# Actuator-MKI-3.net
KiCad netlist of a schematic drawn in EAGLE
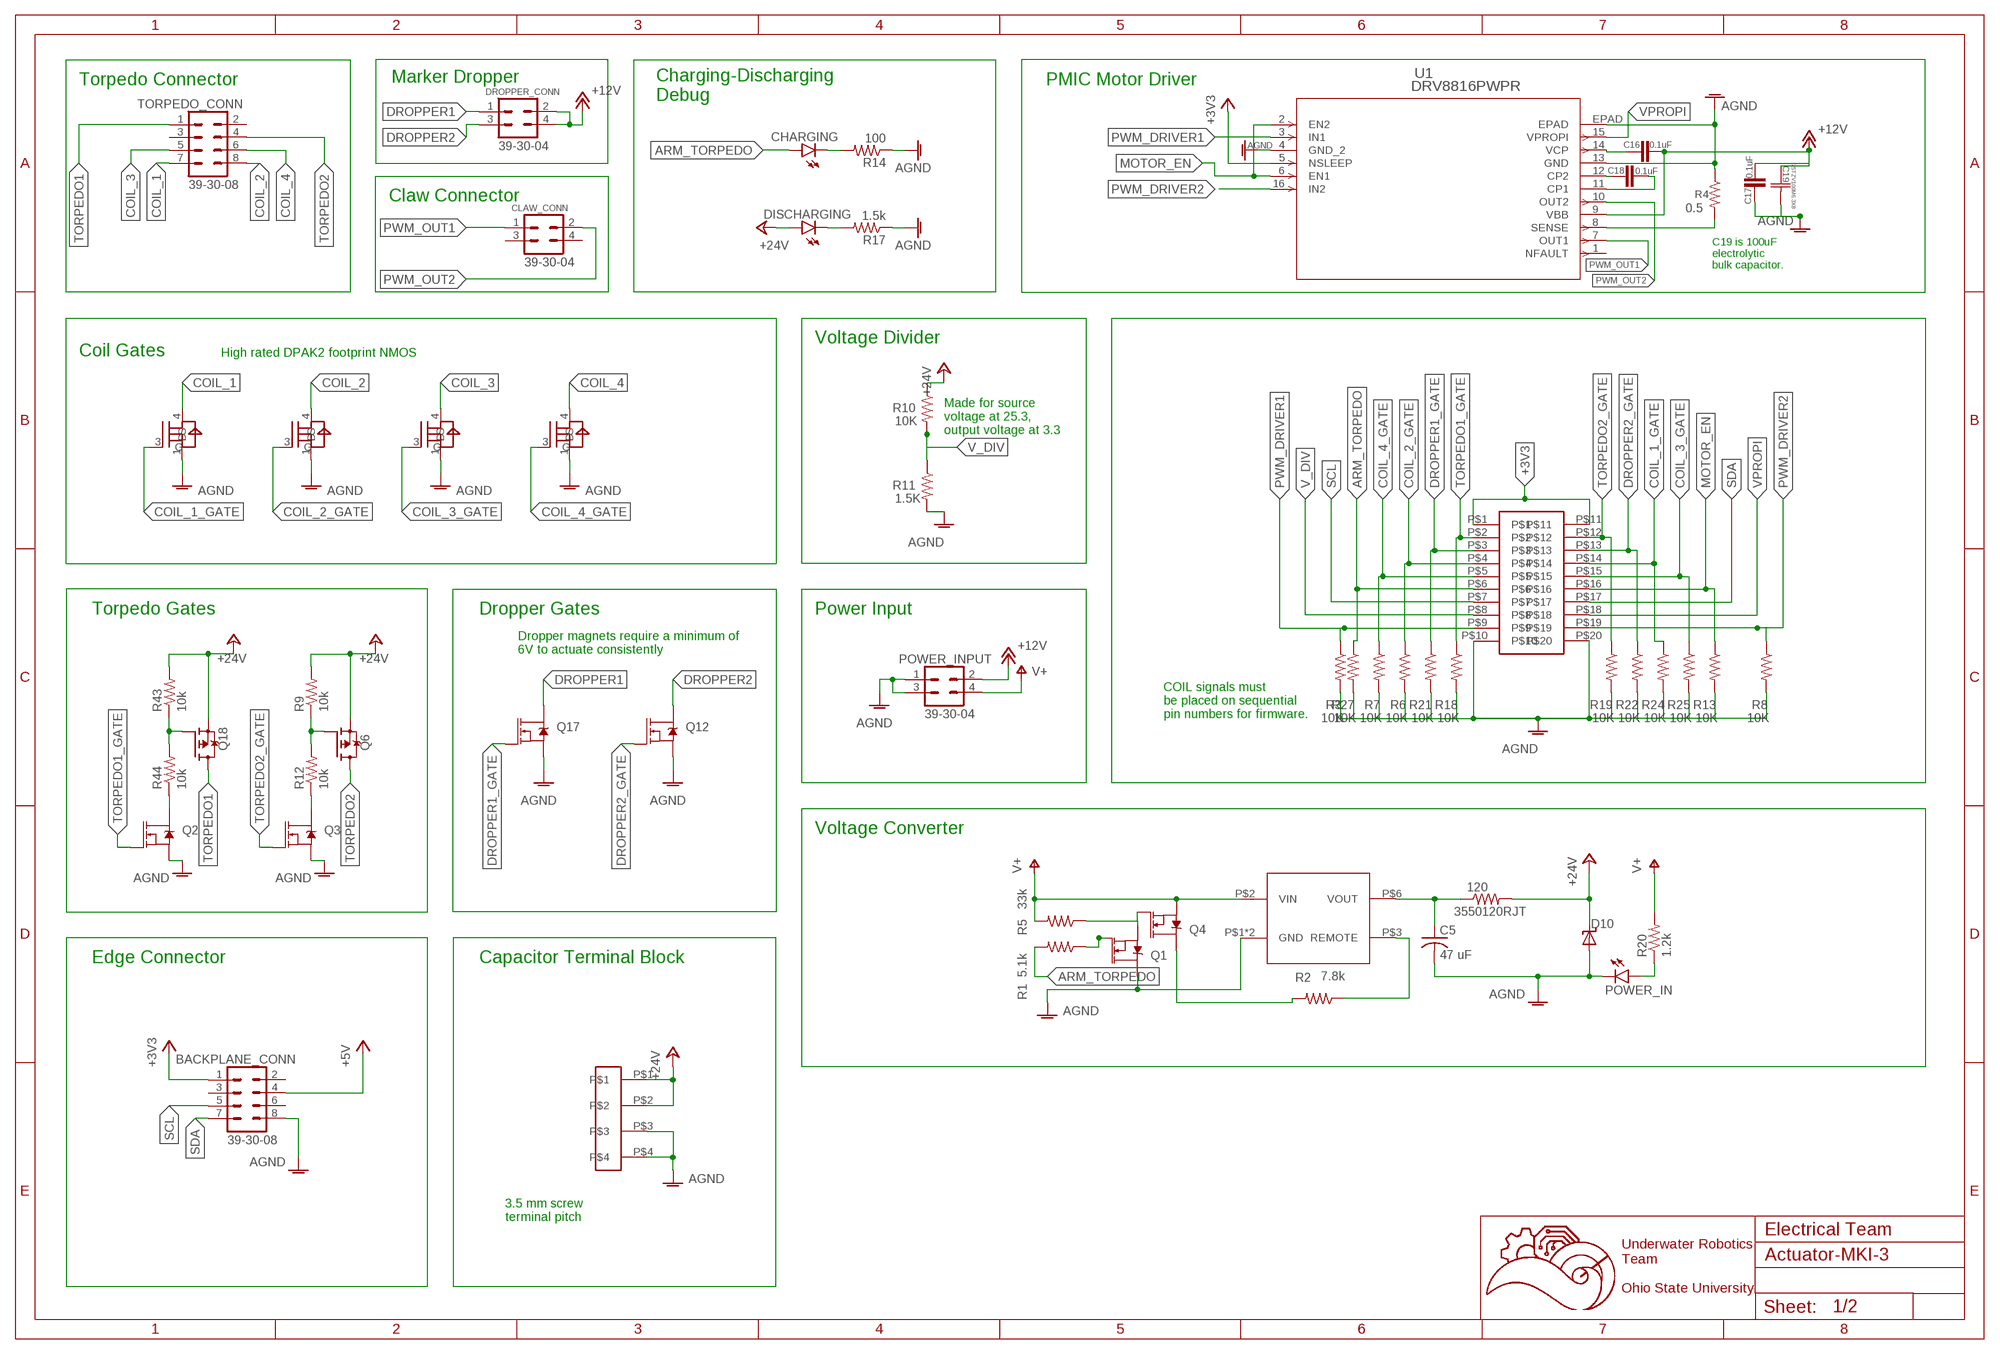
[diagram p0: schematic, sheet 1]
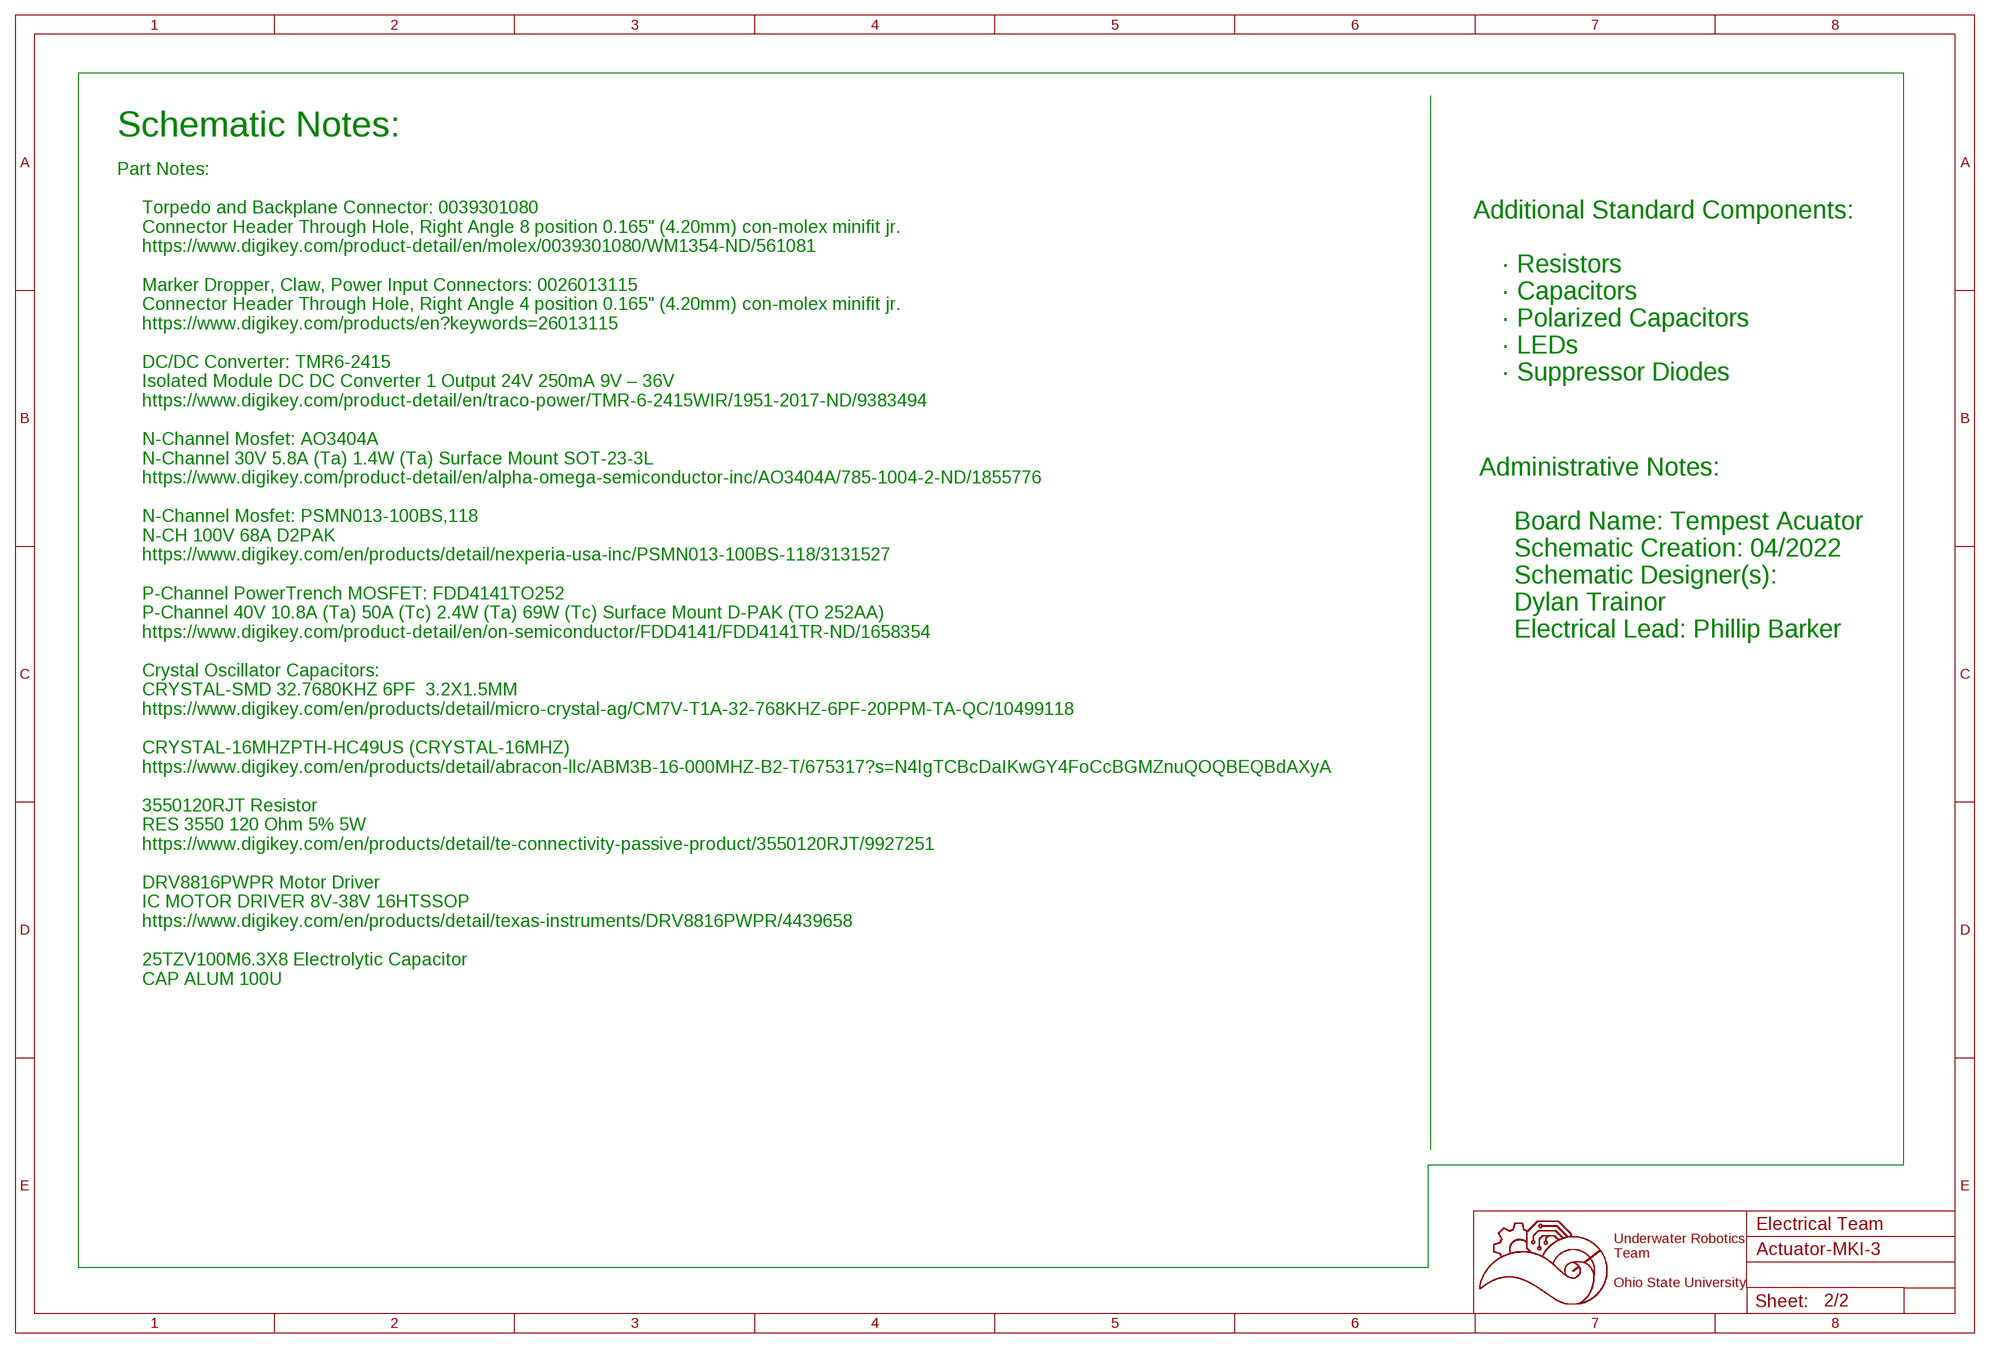
[diagram p1: schematic, sheet 2]

(export (version "E")
  (design (tool "Eeschema 10.0.6"))
  (components
    (comp (ref "120")
      (value "3550120RJT")
      (footprint "eagle-import:3550120RJT")
      (libsource (lib "eagle-import") (part "3550120RJT"))
    )
    (comp (ref "BACKPLANE_CONN")
      (value "39-30-08")
      (footprint "eagle-import:39-30-_08_")
      (libsource (lib "eagle-import") (part "39-30-?08?"))
    )
    (comp (ref "C5")
      (value "47 uF")
      (footprint "eagle-import:C1206K")
      (libsource (lib "eagle-import") (part "C-USC1206K"))
    )
    (comp (ref "C16")
      (value "0.1uF")
      (footprint "eagle-import:C0603")
      (libsource (lib "eagle-import") (part "C-EUC0603"))
    )
    (comp (ref "C17")
      (value "0.1uF")
      (footprint "eagle-import:C0603")
      (libsource (lib "eagle-import") (part "C-EUC0603"))
    )
    (comp (ref "C18")
      (value "0.1uF")
      (footprint "eagle-import:C0603")
      (libsource (lib "eagle-import") (part "C-EUC0603"))
    )
    (comp (ref "C19")
      (value "25TZV100M6.3X8")
      (footprint "eagle-import:CAP_J-V_6P3X8_RUB")
      (fields (field (name "COPYRIGHT") "Copyright (C) 2018 Accelerated Designs. All rights reserved"))
      (libsource (lib "eagle-import") (part "25TZV100M6.3X8"))
    )
    (comp (ref "CHARGING")
      (value "LEDCHIPLED_0603")
      (footprint "eagle-import:CHIPLED_0603")
      (libsource (lib "eagle-import") (part "LEDCHIPLED_0603"))
    )
    (comp (ref "CLAW_CONN")
      (value "39-30-04")
      (footprint "eagle-import:39-30-_04_")
      (libsource (lib "eagle-import") (part "39-30-?04?"))
    )
    (comp (ref "D10")
      (value "SUPPRESSOR-SMBJ")
      (footprint "eagle-import:SMBJ")
      (libsource (lib "eagle-import") (part "SUPPRESSOR-SMBJ"))
    )
    (comp (ref "DISCHARGING")
      (value "LEDCHIPLED_0603")
      (footprint "eagle-import:CHIPLED_0603")
      (libsource (lib "eagle-import") (part "LEDCHIPLED_0603"))
    )
    (comp (ref "DROPPER_CONN")
      (value "39-30-04")
      (footprint "eagle-import:39-30-_04_")
      (libsource (lib "eagle-import") (part "39-30-?04?"))
    )
    (comp (ref "POWER_IN")
      (value "LEDCHIPLED_0603")
      (footprint "eagle-import:CHIPLED_0603")
      (libsource (lib "eagle-import") (part "LEDCHIPLED_0603"))
    )
    (comp (ref "POWER_INPUT")
      (value "39-30-04")
      (footprint "eagle-import:39-30-_04_")
      (libsource (lib "eagle-import") (part "39-30-?04?"))
    )
    (comp (ref "Q1")
      (value "MOSFET-NCH-AO3404A")
      (footprint "eagle-import:SOT23-3")
      (libsource (lib "eagle-import") (part "MOSFET-NCH-AO3404A"))
    )
    (comp (ref "Q2")
      (value "MOSFET-NCH-AO3404A")
      (footprint "eagle-import:SOT23-3")
      (libsource (lib "eagle-import") (part "MOSFET-NCH-AO3404A"))
    )
    (comp (ref "Q3")
      (value "MOSFET-NCH-AO3404A")
      (footprint "eagle-import:SOT23-3")
      (libsource (lib "eagle-import") (part "MOSFET-NCH-AO3404A"))
    )
    (comp (ref "Q4")
      (value "MOSFET-NCH-AO3404A")
      (footprint "eagle-import:SOT23-3")
      (libsource (lib "eagle-import") (part "MOSFET-NCH-AO3404A"))
    )
    (comp (ref "Q6")
      (value "FDD4141TO252")
      (footprint "eagle-import:TO252")
      (libsource (lib "eagle-import") (part "FDD4141TO252"))
    )
    (comp (ref "Q12")
      (value "MOSFET-NCH-AO3404A")
      (footprint "eagle-import:SOT23-3")
      (libsource (lib "eagle-import") (part "MOSFET-NCH-AO3404A"))
    )
    (comp (ref "Q17")
      (value "MOSFET-NCH-AO3404A")
      (footprint "eagle-import:SOT23-3")
      (libsource (lib "eagle-import") (part "MOSFET-NCH-AO3404A"))
    )
    (comp (ref "Q18")
      (value "FDD4141TO252")
      (footprint "eagle-import:TO252")
      (libsource (lib "eagle-import") (part "FDD4141TO252"))
    )
    (comp (ref "R1")
      (value "5.1k")
      (footprint "eagle-import:R0603")
      (libsource (lib "eagle-import") (part "R-US_R0603"))
    )
    (comp (ref "R2")
      (value "7.8k")
      (footprint "eagle-import:R0603")
      (libsource (lib "eagle-import") (part "R-US_R0603"))
    )
    (comp (ref "R3")
      (value "10K")
      (footprint "eagle-import:R0603")
      (libsource (lib "eagle-import") (part "R-US_R0603"))
    )
    (comp (ref "R4")
      (value "0.5")
      (footprint "eagle-import:R0805")
      (libsource (lib "eagle-import") (part "R-US_R0805"))
    )
    (comp (ref "R5")
      (value "33k")
      (footprint "eagle-import:R0603")
      (libsource (lib "eagle-import") (part "R-US_R0603"))
    )
    (comp (ref "R6")
      (value "10K")
      (footprint "eagle-import:R0603")
      (libsource (lib "eagle-import") (part "R-US_R0603"))
    )
    (comp (ref "R7")
      (value "10K")
      (footprint "eagle-import:R0603")
      (libsource (lib "eagle-import") (part "R-US_R0603"))
    )
    (comp (ref "R8")
      (value "10K")
      (footprint "eagle-import:R0603")
      (libsource (lib "eagle-import") (part "R-US_R0603"))
    )
    (comp (ref "R9")
      (value "10k")
      (footprint "eagle-import:R0603")
      (libsource (lib "eagle-import") (part "R-US_R0603"))
    )
    (comp (ref "R10")
      (value "10K")
      (footprint "eagle-import:R0603")
      (libsource (lib "eagle-import") (part "R-US_R0603"))
    )
    (comp (ref "R11")
      (value "1.5K")
      (footprint "eagle-import:R0603")
      (libsource (lib "eagle-import") (part "R-US_R0603"))
    )
    (comp (ref "R12")
      (value "10k")
      (footprint "eagle-import:R0603")
      (libsource (lib "eagle-import") (part "R-US_R0603"))
    )
    (comp (ref "R13")
      (value "10K")
      (footprint "eagle-import:R0603")
      (libsource (lib "eagle-import") (part "R-US_R0603"))
    )
    (comp (ref "R14")
      (value "100")
      (footprint "eagle-import:R0805")
      (libsource (lib "eagle-import") (part "R-US_R0805"))
    )
    (comp (ref "R17")
      (value "1.5k")
      (footprint "eagle-import:R0805")
      (libsource (lib "eagle-import") (part "R-US_R0805"))
    )
    (comp (ref "R18")
      (value "10K")
      (footprint "eagle-import:R0603")
      (libsource (lib "eagle-import") (part "R-US_R0603"))
    )
    (comp (ref "R19")
      (value "10K")
      (footprint "eagle-import:R0603")
      (libsource (lib "eagle-import") (part "R-US_R0603"))
    )
    (comp (ref "R20")
      (value "1.2k")
      (footprint "eagle-import:R0805")
      (libsource (lib "eagle-import") (part "R-US_R0805"))
    )
    (comp (ref "R21")
      (value "10K")
      (footprint "eagle-import:R0603")
      (libsource (lib "eagle-import") (part "R-US_R0603"))
    )
    (comp (ref "R22")
      (value "10K")
      (footprint "eagle-import:R0603")
      (libsource (lib "eagle-import") (part "R-US_R0603"))
    )
    (comp (ref "R24")
      (value "10K")
      (footprint "eagle-import:R0603")
      (libsource (lib "eagle-import") (part "R-US_R0603"))
    )
    (comp (ref "R25")
      (value "10K")
      (footprint "eagle-import:R0603")
      (libsource (lib "eagle-import") (part "R-US_R0603"))
    )
    (comp (ref "R27")
      (value "10K")
      (footprint "eagle-import:R0603")
      (libsource (lib "eagle-import") (part "R-US_R0603"))
    )
    (comp (ref "R43")
      (value "10k")
      (footprint "eagle-import:R0603")
      (libsource (lib "eagle-import") (part "R-US_R0603"))
    )
    (comp (ref "R44")
      (value "10k")
      (footprint "eagle-import:R0603")
      (libsource (lib "eagle-import") (part "R-US_R0603"))
    )
    (comp (ref "TORPEDO_CONN")
      (value "39-30-08")
      (footprint "eagle-import:39-30-_08_")
      (libsource (lib "eagle-import") (part "39-30-?08?"))
    )
    (comp (ref "U$1")
      (value "31059104")
      (footprint "eagle-import:31059104")
      (libsource (lib "eagle-import") (part "31059104"))
    )
    (comp (ref "U$2")
      (value "JTAG-SMD")
      (footprint "eagle-import:JTAG-SMD")
      (libsource (lib "eagle-import") (part "JTAG-SMD"))
    )
    (comp (ref "U$6")
      (value "TMR6-2415")
      (footprint "eagle-import:TMR6-2415")
      (libsource (lib "eagle-import") (part "TMR6-2415"))
    )
    (comp (ref "U1")
      (value "DRV8816PWPR")
      (footprint "eagle-import:PWP_16")
      (libsource (lib "eagle-import") (part "DRV8816PWPR"))
    )
    (comp (ref "U2")
      (value "MBRB2060CTT4G")
      (footprint "eagle-import:D2PAK3-4_9P65X10P29_ONS")
      (libsource (lib "eagle-import") (part "MBRB2060CTT4G"))
    )
    (comp (ref "U3")
      (value "MBRB2060CTT4G")
      (footprint "eagle-import:D2PAK3-4_9P65X10P29_ONS")
      (libsource (lib "eagle-import") (part "MBRB2060CTT4G"))
    )
    (comp (ref "U4")
      (value "MBRB2060CTT4G")
      (footprint "eagle-import:D2PAK3-4_9P65X10P29_ONS")
      (libsource (lib "eagle-import") (part "MBRB2060CTT4G"))
    )
    (comp (ref "U5")
      (value "MBRB2060CTT4G")
      (footprint "eagle-import:D2PAK3-4_9P65X10P29_ONS")
      (libsource (lib "eagle-import") (part "MBRB2060CTT4G"))
    )
  )
  (nets
    (net (code "1") (name "+3V3") (class "Default")
      (node (ref "BACKPLANE_CONN") (pin "1") (pinfunction "1_1") (pintype "passive"))
      (node (ref "U$2") (pin "P$1") (pinfunction "P$1_P$1") (pintype "bidirectional"))
      (node (ref "U$2") (pin "P$11") (pinfunction "P$11_P$11") (pintype "bidirectional"))
      (node (ref "U1") (pin "5") (pinfunction "NSLEEP_5") (pintype "input"))
    )
    (net (code "2") (name "+5V") (class "Default")
      (node (ref "BACKPLANE_CONN") (pin "4") (pinfunction "4_4") (pintype "passive"))
    )
    (net (code "3") (name "+12V") (class "Default")
      (node (ref "C16") (pin "2") (pinfunction "2_2") (pintype "passive"))
      (node (ref "C17") (pin "2") (pinfunction "2_2") (pintype "passive"))
      (node (ref "C19") (pin "1") (pinfunction "1_1") (pintype "passive"))
      (node (ref "DROPPER_CONN") (pin "2") (pinfunction "2_2") (pintype "passive"))
      (node (ref "DROPPER_CONN") (pin "4") (pinfunction "4_4") (pintype "passive"))
      (node (ref "POWER_INPUT") (pin "2") (pinfunction "2_2") (pintype "passive"))
      (node (ref "U1") (pin "9") (pinfunction "VBB_9") (pintype "power_in"))
    )
    (net (code "4") (name "+24V") (class "Default")
      (node (ref "120") (pin "P$2") (pinfunction "2_P$2") (pintype "passive"))
      (node (ref "D10") (pin "C") (pinfunction "C_C") (pintype "passive"))
      (node (ref "DISCHARGING") (pin "A") (pinfunction "A_A") (pintype "passive"))
      (node (ref "Q18") (pin "2") (pinfunction "S_2") (pintype "passive"))
      (node (ref "Q6") (pin "2") (pinfunction "S_2") (pintype "passive"))
      (node (ref "R10") (pin "1") (pinfunction "1_1") (pintype "passive"))
      (node (ref "R43") (pin "2") (pinfunction "2_2") (pintype "passive"))
      (node (ref "R9") (pin "2") (pinfunction "2_2") (pintype "passive"))
      (node (ref "U$1") (pin "P$1") (pinfunction "P$1_P$1") (pintype "bidirectional"))
      (node (ref "U$1") (pin "P$2") (pinfunction "P$2_P$2") (pintype "bidirectional"))
    )
    (net (code "5") (name "AGND") (class "Default")
      (node (ref "BACKPLANE_CONN") (pin "8") (pinfunction "8_8") (pintype "passive"))
      (node (ref "C17") (pin "1") (pinfunction "1_1") (pintype "passive"))
      (node (ref "C19") (pin "2") (pinfunction "2_2") (pintype "passive"))
      (node (ref "C5") (pin "2") (pinfunction "2_2") (pintype "passive"))
      (node (ref "D10") (pin "A") (pinfunction "A_A") (pintype "passive"))
      (node (ref "POWER_IN") (pin "C") (pinfunction "C_C") (pintype "passive"))
      (node (ref "POWER_INPUT") (pin "1") (pinfunction "1_1") (pintype "passive"))
      (node (ref "POWER_INPUT") (pin "3") (pinfunction "3_3") (pintype "passive"))
      (node (ref "Q1") (pin "3") (pinfunction "D_3") (pintype "bidirectional"))
      (node (ref "Q12") (pin "2") (pinfunction "S_2") (pintype "bidirectional"))
      (node (ref "Q17") (pin "2") (pinfunction "S_2") (pintype "bidirectional"))
      (node (ref "Q2") (pin "2") (pinfunction "S_2") (pintype "bidirectional"))
      (node (ref "Q3") (pin "2") (pinfunction "S_2") (pintype "bidirectional"))
      (node (ref "R11") (pin "2") (pinfunction "2_2") (pintype "passive"))
      (node (ref "R13") (pin "2") (pinfunction "2_2") (pintype "passive"))
      (node (ref "R14") (pin "1") (pinfunction "1_1") (pintype "passive"))
      (node (ref "R17") (pin "1") (pinfunction "1_1") (pintype "passive"))
      (node (ref "R18") (pin "2") (pinfunction "2_2") (pintype "passive"))
      (node (ref "R19") (pin "2") (pinfunction "2_2") (pintype "passive"))
      (node (ref "R21") (pin "2") (pinfunction "2_2") (pintype "passive"))
      (node (ref "R22") (pin "2") (pinfunction "2_2") (pintype "passive"))
      (node (ref "R24") (pin "2") (pinfunction "2_2") (pintype "passive"))
      (node (ref "R25") (pin "2") (pinfunction "2_2") (pintype "passive"))
      (node (ref "R27") (pin "2") (pinfunction "2_2") (pintype "passive"))
      (node (ref "R3") (pin "2") (pinfunction "2_2") (pintype "passive"))
      (node (ref "R4") (pin "1") (pinfunction "1_1") (pintype "passive"))
      (node (ref "R6") (pin "2") (pinfunction "2_2") (pintype "passive"))
      (node (ref "R7") (pin "2") (pinfunction "2_2") (pintype "passive"))
      (node (ref "R8") (pin "2") (pinfunction "2_2") (pintype "passive"))
      (node (ref "U$1") (pin "P$3") (pinfunction "P$3_P$3") (pintype "bidirectional"))
      (node (ref "U$1") (pin "P$4") (pinfunction "P$4_P$4") (pintype "bidirectional"))
      (node (ref "U$2") (pin "P$10") (pinfunction "P$10_P$10") (pintype "bidirectional"))
      (node (ref "U$2") (pin "P$20") (pinfunction "P$20_P$20") (pintype "bidirectional"))
      (node (ref "U$6") (pin "P$1") (pinfunction "GND_P$1") (pintype "bidirectional"))
      (node (ref "U$6") (pin "P$7") (pinfunction "GND_P$7") (pintype "bidirectional"))
      (node (ref "U1") (pin "13") (pinfunction "GND_13") (pintype "power_in"))
      (node (ref "U1") (pin "4") (pinfunction "GND_2_4") (pintype "power_in"))
      (node (ref "U1") (pin "EPAD") (pinfunction "EPAD_EPAD") (pintype "passive"))
      (node (ref "U2") (pin "1") (pinfunction "S_1") (pintype "bidirectional"))
      (node (ref "U3") (pin "1") (pinfunction "S_1") (pintype "bidirectional"))
      (node (ref "U4") (pin "1") (pinfunction "S_1") (pintype "bidirectional"))
      (node (ref "U5") (pin "1") (pinfunction "S_1") (pintype "bidirectional"))
    )
    (net (code "6") (name "ARM_TORPEDO") (class "Default")
      (node (ref "CHARGING") (pin "A") (pinfunction "A_A") (pintype "passive"))
      (node (ref "R1") (pin "2") (pinfunction "2_2") (pintype "passive"))
      (node (ref "R27") (pin "1") (pinfunction "1_1") (pintype "passive"))
      (node (ref "U$2") (pin "P$6") (pinfunction "P$6_P$6") (pintype "bidirectional"))
    )
    (net (code "7") (name "COIL_1") (class "Default")
      (node (ref "TORPEDO_CONN") (pin "7") (pinfunction "7_7") (pintype "passive"))
      (node (ref "U2") (pin "4") (pinfunction "D_4") (pintype "bidirectional"))
    )
    (net (code "8") (name "COIL_1_GATE") (class "Default")
      (node (ref "R24") (pin "1") (pinfunction "1_1") (pintype "passive"))
      (node (ref "U$2") (pin "P$14") (pinfunction "P$14_P$14") (pintype "bidirectional"))
      (node (ref "U2") (pin "3") (pinfunction "G_3") (pintype "bidirectional"))
    )
    (net (code "9") (name "COIL_2") (class "Default")
      (node (ref "TORPEDO_CONN") (pin "8") (pinfunction "8_8") (pintype "passive"))
      (node (ref "U3") (pin "4") (pinfunction "D_4") (pintype "bidirectional"))
    )
    (net (code "10") (name "COIL_2_GATE") (class "Default")
      (node (ref "R6") (pin "1") (pinfunction "1_1") (pintype "passive"))
      (node (ref "U$2") (pin "P$4") (pinfunction "P$4_P$4") (pintype "bidirectional"))
      (node (ref "U3") (pin "3") (pinfunction "G_3") (pintype "bidirectional"))
    )
    (net (code "11") (name "COIL_3") (class "Default")
      (node (ref "TORPEDO_CONN") (pin "5") (pinfunction "5_5") (pintype "passive"))
      (node (ref "U4") (pin "4") (pinfunction "D_4") (pintype "bidirectional"))
    )
    (net (code "12") (name "COIL_3_GATE") (class "Default")
      (node (ref "R25") (pin "1") (pinfunction "1_1") (pintype "passive"))
      (node (ref "U$2") (pin "P$15") (pinfunction "P$15_P$15") (pintype "bidirectional"))
      (node (ref "U4") (pin "3") (pinfunction "G_3") (pintype "bidirectional"))
    )
    (net (code "13") (name "COIL_4") (class "Default")
      (node (ref "TORPEDO_CONN") (pin "6") (pinfunction "6_6") (pintype "passive"))
      (node (ref "U5") (pin "4") (pinfunction "D_4") (pintype "bidirectional"))
    )
    (net (code "14") (name "COIL_4_GATE") (class "Default")
      (node (ref "R7") (pin "1") (pinfunction "1_1") (pintype "passive"))
      (node (ref "U$2") (pin "P$5") (pinfunction "P$5_P$5") (pintype "bidirectional"))
      (node (ref "U5") (pin "3") (pinfunction "G_3") (pintype "bidirectional"))
    )
    (net (code "15") (name "DROPPER1") (class "Default")
      (node (ref "DROPPER_CONN") (pin "1") (pinfunction "1_1") (pintype "passive"))
      (node (ref "Q17") (pin "3") (pinfunction "D_3") (pintype "bidirectional"))
    )
    (net (code "16") (name "DROPPER1_GATE") (class "Default")
      (node (ref "Q17") (pin "1") (pinfunction "G_1") (pintype "bidirectional"))
      (node (ref "R21") (pin "1") (pinfunction "1_1") (pintype "passive"))
      (node (ref "U$2") (pin "P$3") (pinfunction "P$3_P$3") (pintype "bidirectional"))
    )
    (net (code "17") (name "DROPPER2") (class "Default")
      (node (ref "DROPPER_CONN") (pin "3") (pinfunction "3_3") (pintype "passive"))
      (node (ref "Q12") (pin "3") (pinfunction "D_3") (pintype "bidirectional"))
    )
    (net (code "18") (name "DROPPER2_GATE") (class "Default")
      (node (ref "Q12") (pin "1") (pinfunction "G_1") (pintype "bidirectional"))
      (node (ref "R22") (pin "1") (pinfunction "1_1") (pintype "passive"))
      (node (ref "U$2") (pin "P$13") (pinfunction "P$13_P$13") (pintype "bidirectional"))
    )
    (net (code "19") (name "MOTOR_EN") (class "Default")
      (node (ref "R13") (pin "1") (pinfunction "1_1") (pintype "passive"))
      (node (ref "U$2") (pin "P$16") (pinfunction "P$16_P$16") (pintype "bidirectional"))
      (node (ref "U1") (pin "2") (pinfunction "EN2_2") (pintype "input"))
      (node (ref "U1") (pin "6") (pinfunction "EN1_6") (pintype "input"))
    )
    (net (code "20") (name "Net-(120-1)") (class "Default")
      (node (ref "120") (pin "P$1") (pinfunction "1_P$1") (pintype "passive"))
      (node (ref "C5") (pin "1") (pinfunction "1_1") (pintype "passive"))
      (node (ref "U$6") (pin "P$6") (pinfunction "VOUT_P$6") (pintype "bidirectional"))
    )
    (net (code "21") (name "Net-(CHARGING-PadC)") (class "Default")
      (node (ref "CHARGING") (pin "C") (pinfunction "C_C") (pintype "passive"))
      (node (ref "R14") (pin "2") (pinfunction "2_2") (pintype "passive"))
    )
    (net (code "22") (name "Net-(DISCHARGING-PadC)") (class "Default")
      (node (ref "DISCHARGING") (pin "C") (pinfunction "C_C") (pintype "passive"))
      (node (ref "R17") (pin "2") (pinfunction "2_2") (pintype "passive"))
    )
    (net (code "23") (name "Net-(POWER_IN-PadA)") (class "Default")
      (node (ref "POWER_IN") (pin "A") (pinfunction "A_A") (pintype "passive"))
      (node (ref "R20") (pin "1") (pinfunction "1_1") (pintype "passive"))
    )
    (net (code "24") (name "Net-(Q1-G)") (class "Default")
      (node (ref "Q1") (pin "1") (pinfunction "G_1") (pintype "bidirectional"))
      (node (ref "R1") (pin "1") (pinfunction "1_1") (pintype "passive"))
    )
    (net (code "25") (name "Net-(Q1-S)") (class "Default")
      (node (ref "Q1") (pin "2") (pinfunction "S_2") (pintype "bidirectional"))
      (node (ref "Q4") (pin "1") (pinfunction "G_1") (pintype "bidirectional"))
      (node (ref "R5") (pin "1") (pinfunction "1_1") (pintype "passive"))
    )
    (net (code "26") (name "Net-(Q2-D)") (class "Default")
      (node (ref "Q2") (pin "3") (pinfunction "D_3") (pintype "bidirectional"))
      (node (ref "R44") (pin "1") (pinfunction "1_1") (pintype "passive"))
    )
    (net (code "27") (name "Net-(Q3-D)") (class "Default")
      (node (ref "Q3") (pin "3") (pinfunction "D_3") (pintype "bidirectional"))
      (node (ref "R12") (pin "1") (pinfunction "1_1") (pintype "passive"))
    )
    (net (code "28") (name "Net-(Q4-D)") (class "Default")
      (node (ref "Q4") (pin "3") (pinfunction "D_3") (pintype "bidirectional"))
      (node (ref "R2") (pin "2") (pinfunction "2_2") (pintype "passive"))
    )
    (net (code "29") (name "Net-(Q6-G)") (class "Default")
      (node (ref "Q6") (pin "1") (pinfunction "G_1") (pintype "passive"))
      (node (ref "R12") (pin "2") (pinfunction "2_2") (pintype "passive"))
      (node (ref "R9") (pin "1") (pinfunction "1_1") (pintype "passive"))
    )
    (net (code "30") (name "Net-(Q18-G)") (class "Default")
      (node (ref "Q18") (pin "1") (pinfunction "G_1") (pintype "passive"))
      (node (ref "R43") (pin "1") (pinfunction "1_1") (pintype "passive"))
      (node (ref "R44") (pin "2") (pinfunction "2_2") (pintype "passive"))
    )
    (net (code "31") (name "Net-(U$6-REMOTE)") (class "Default")
      (node (ref "R2") (pin "1") (pinfunction "1_1") (pintype "passive"))
      (node (ref "U$6") (pin "P$3") (pinfunction "REMOTE_P$3") (pintype "bidirectional"))
    )
    (net (code "32") (name "Net-(U1-CP1)") (class "Default")
      (node (ref "C18") (pin "2") (pinfunction "2_2") (pintype "passive"))
      (node (ref "U1") (pin "11") (pinfunction "CP1_11") (pintype "passive"))
    )
    (net (code "33") (name "Net-(U1-CP2)") (class "Default")
      (node (ref "C18") (pin "1") (pinfunction "1_1") (pintype "passive"))
      (node (ref "U1") (pin "12") (pinfunction "CP2_12") (pintype "passive"))
    )
    (net (code "34") (name "Net-(U1-SENSE)") (class "Default")
      (node (ref "R4") (pin "2") (pinfunction "2_2") (pintype "passive"))
      (node (ref "U1") (pin "8") (pinfunction "SENSE_8") (pintype "output"))
    )
    (net (code "35") (name "Net-(U1-VCP)") (class "Default")
      (node (ref "C16") (pin "1") (pinfunction "1_1") (pintype "passive"))
      (node (ref "U1") (pin "14") (pinfunction "VCP_14") (pintype "output"))
    )
    (net (code "36") (name "PWM_DRIVER1") (class "Default")
      (node (ref "R3") (pin "1") (pinfunction "1_1") (pintype "passive"))
      (node (ref "U$2") (pin "P$9") (pinfunction "P$9_P$9") (pintype "bidirectional"))
      (node (ref "U1") (pin "3") (pinfunction "IN1_3") (pintype "input"))
    )
    (net (code "37") (name "PWM_DRIVER2") (class "Default")
      (node (ref "R8") (pin "1") (pinfunction "1_1") (pintype "passive"))
      (node (ref "U$2") (pin "P$19") (pinfunction "P$19_P$19") (pintype "bidirectional"))
      (node (ref "U1") (pin "16") (pinfunction "IN2_16") (pintype "input"))
    )
    (net (code "38") (name "PWM_OUT1") (class "Default")
      (node (ref "CLAW_CONN") (pin "1") (pinfunction "1_1") (pintype "passive"))
      (node (ref "U1") (pin "7") (pinfunction "OUT1_7") (pintype "output"))
    )
    (net (code "39") (name "PWM_OUT2") (class "Default")
      (node (ref "CLAW_CONN") (pin "2") (pinfunction "2_2") (pintype "passive"))
      (node (ref "U1") (pin "10") (pinfunction "OUT2_10") (pintype "output"))
    )
    (net (code "40") (name "SCL") (class "Default")
      (node (ref "BACKPLANE_CONN") (pin "5") (pinfunction "5_5") (pintype "passive"))
      (node (ref "U$2") (pin "P$7") (pinfunction "P$7_P$7") (pintype "bidirectional"))
    )
    (net (code "41") (name "SDA") (class "Default")
      (node (ref "BACKPLANE_CONN") (pin "7") (pinfunction "7_7") (pintype "passive"))
      (node (ref "U$2") (pin "P$17") (pinfunction "P$17_P$17") (pintype "bidirectional"))
    )
    (net (code "42") (name "TORPEDO1") (class "Default")
      (node (ref "Q18") (pin "3") (pinfunction "D_3") (pintype "passive"))
      (node (ref "TORPEDO_CONN") (pin "1") (pinfunction "1_1") (pintype "passive"))
    )
    (net (code "43") (name "TORPEDO1_GATE") (class "Default")
      (node (ref "Q2") (pin "1") (pinfunction "G_1") (pintype "bidirectional"))
      (node (ref "R18") (pin "1") (pinfunction "1_1") (pintype "passive"))
      (node (ref "U$2") (pin "P$2") (pinfunction "P$2_P$2") (pintype "bidirectional"))
    )
    (net (code "44") (name "TORPEDO2") (class "Default")
      (node (ref "Q6") (pin "3") (pinfunction "D_3") (pintype "passive"))
      (node (ref "TORPEDO_CONN") (pin "4") (pinfunction "4_4") (pintype "passive"))
    )
    (net (code "45") (name "TORPEDO2_GATE") (class "Default")
      (node (ref "Q3") (pin "1") (pinfunction "G_1") (pintype "bidirectional"))
      (node (ref "R19") (pin "1") (pinfunction "1_1") (pintype "passive"))
      (node (ref "U$2") (pin "P$12") (pinfunction "P$12_P$12") (pintype "bidirectional"))
    )
    (net (code "46") (name "V+") (class "Default")
      (node (ref "POWER_INPUT") (pin "4") (pinfunction "4_4") (pintype "passive"))
      (node (ref "Q4") (pin "2") (pinfunction "S_2") (pintype "bidirectional"))
      (node (ref "R20") (pin "2") (pinfunction "2_2") (pintype "passive"))
      (node (ref "R5") (pin "2") (pinfunction "2_2") (pintype "passive"))
      (node (ref "U$6") (pin "P$2") (pinfunction "VIN_P$2") (pintype "bidirectional"))
    )
    (net (code "47") (name "VPROPI") (class "Default")
      (node (ref "U$2") (pin "P$18") (pinfunction "P$18_P$18") (pintype "bidirectional"))
      (node (ref "U1") (pin "15") (pinfunction "VPROPI_15") (pintype "output"))
    )
    (net (code "48") (name "V_DIV") (class "Default")
      (node (ref "R10") (pin "2") (pinfunction "2_2") (pintype "passive"))
      (node (ref "R11") (pin "1") (pinfunction "1_1") (pintype "passive"))
      (node (ref "U$2") (pin "P$8") (pinfunction "P$8_P$8") (pintype "bidirectional"))
    )
    (net (code "49") (name "unconnected-(BACKPLANE_CONN-Pad2)") (class "Default")
      (node (ref "BACKPLANE_CONN") (pin "2") (pinfunction "2_2") (pintype "passive"))
    )
    (net (code "50") (name "unconnected-(BACKPLANE_CONN-Pad3)") (class "Default")
      (node (ref "BACKPLANE_CONN") (pin "3") (pinfunction "3_3") (pintype "passive"))
    )
    (net (code "51") (name "unconnected-(BACKPLANE_CONN-Pad6)") (class "Default")
      (node (ref "BACKPLANE_CONN") (pin "6") (pinfunction "6_6") (pintype "passive"))
    )
    (net (code "52") (name "unconnected-(CLAW_CONN-Pad3)") (class "Default")
      (node (ref "CLAW_CONN") (pin "3") (pinfunction "3_3") (pintype "passive"))
    )
    (net (code "53") (name "unconnected-(CLAW_CONN-Pad4)") (class "Default")
      (node (ref "CLAW_CONN") (pin "4") (pinfunction "4_4") (pintype "passive"))
    )
    (net (code "54") (name "unconnected-(TORPEDO_CONN-Pad2)") (class "Default")
      (node (ref "TORPEDO_CONN") (pin "2") (pinfunction "2_2") (pintype "passive"))
    )
    (net (code "55") (name "unconnected-(TORPEDO_CONN-Pad3)") (class "Default")
      (node (ref "TORPEDO_CONN") (pin "3") (pinfunction "3_3") (pintype "passive"))
    )
    (net (code "56") (name "unconnected-(U1-NFAULT-Pad1)") (class "Default")
      (node (ref "U1") (pin "1") (pinfunction "NFAULT_1") (pintype "output"))
    )
  )
)
